# untitled.net
KiCad netlist of a schematic drawn in EAGLE
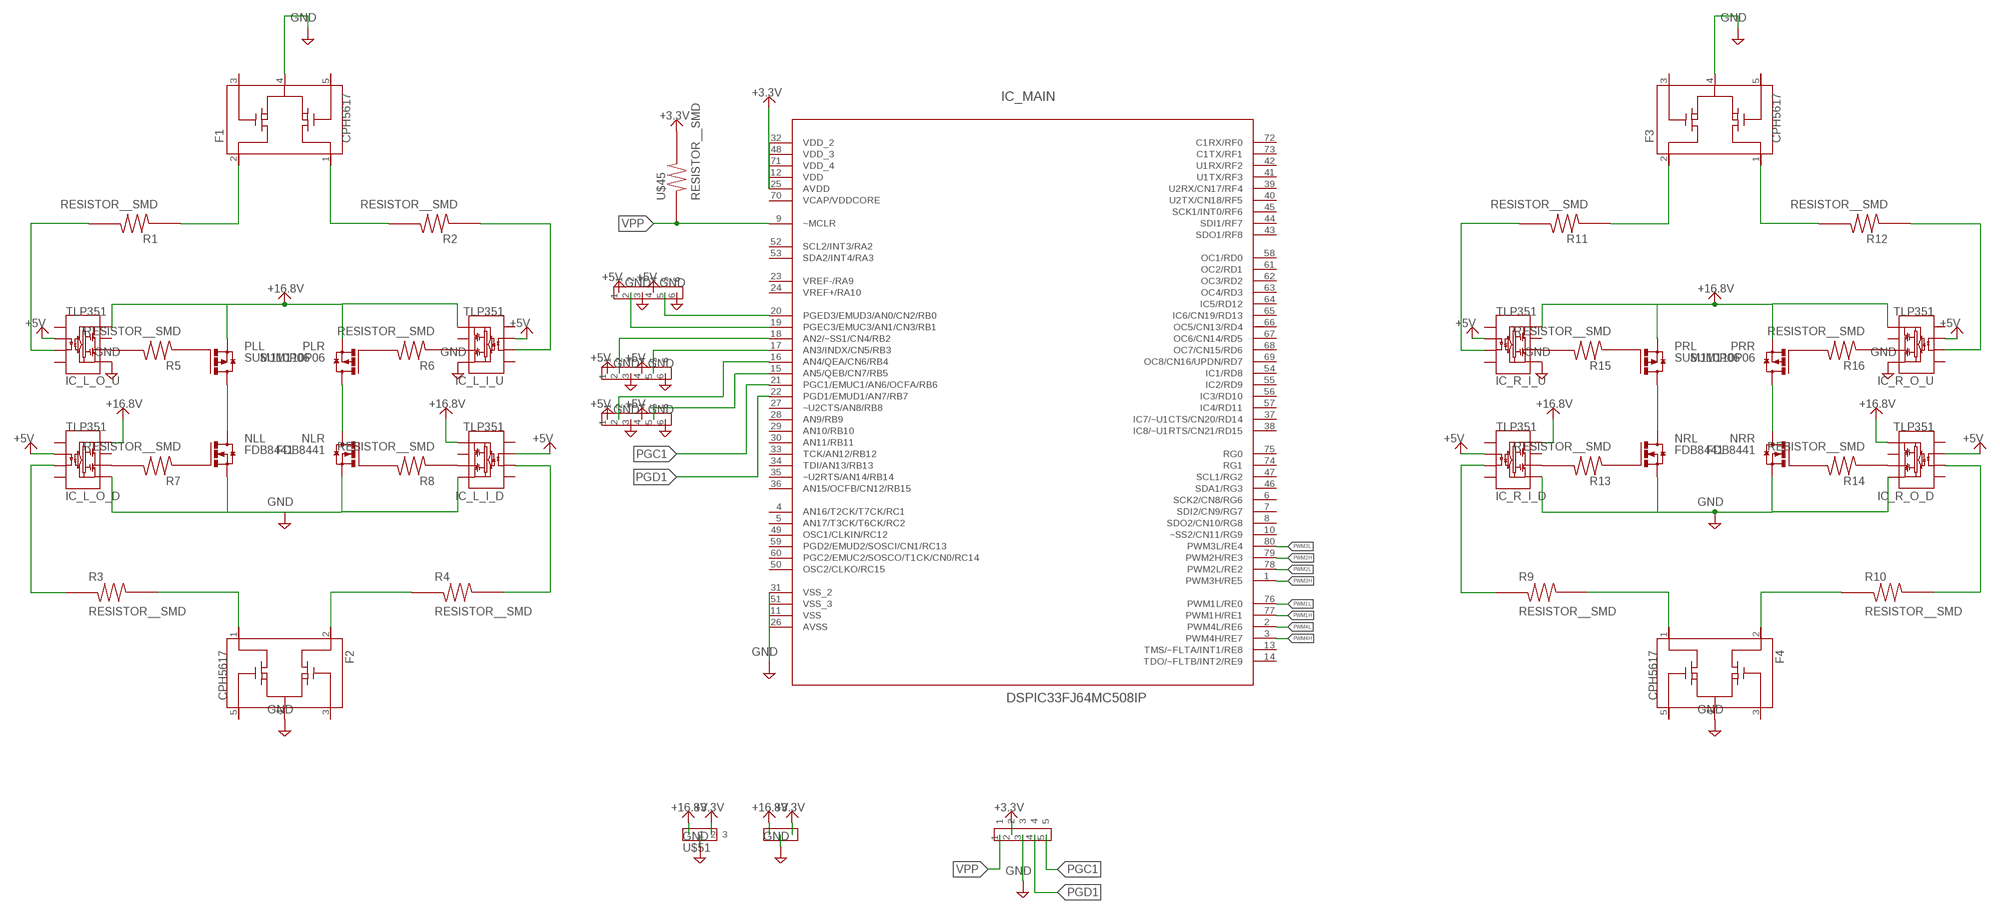
[diagram p0: schematic, sheet 1]

(export (version "E")
  (design (tool "Eeschema 10.0.6"))
  (components
    (comp (ref "F1")
      (value "CPH5617")
      (footprint "eagle-import:CHP-5")
      (libsource (lib "eagle-import") (part "CPH5617"))
    )
    (comp (ref "F2")
      (value "CPH5617")
      (footprint "eagle-import:CHP-5")
      (libsource (lib "eagle-import") (part "CPH5617"))
    )
    (comp (ref "F3")
      (value "CPH5617")
      (footprint "eagle-import:CHP-5")
      (libsource (lib "eagle-import") (part "CPH5617"))
    )
    (comp (ref "F4")
      (value "CPH5617")
      (footprint "eagle-import:CHP-5")
      (libsource (lib "eagle-import") (part "CPH5617"))
    )
    (comp (ref "IC_L_I_D")
      (value "TLP351")
      (footprint "eagle-import:DIL08")
      (libsource (lib "eagle-import") (part "TLP351"))
    )
    (comp (ref "IC_L_I_U")
      (value "TLP351")
      (footprint "eagle-import:DIL08")
      (libsource (lib "eagle-import") (part "TLP351"))
    )
    (comp (ref "IC_L_O_D")
      (value "TLP351")
      (footprint "eagle-import:DIL08")
      (libsource (lib "eagle-import") (part "TLP351"))
    )
    (comp (ref "IC_L_O_U")
      (value "TLP351")
      (footprint "eagle-import:DIL08")
      (libsource (lib "eagle-import") (part "TLP351"))
    )
    (comp (ref "IC_MAIN")
      (value "DSPIC33FJ64MC508IP")
      (footprint "eagle-import:QFP50P1400X1400X120-80N")
      (libsource (lib "eagle-import") (part "DSPIC33FJ64MC508IP"))
    )
    (comp (ref "IC_R_I_D")
      (value "TLP351")
      (footprint "eagle-import:DIL08")
      (libsource (lib "eagle-import") (part "TLP351"))
    )
    (comp (ref "IC_R_I_U")
      (value "TLP351")
      (footprint "eagle-import:DIL08")
      (libsource (lib "eagle-import") (part "TLP351"))
    )
    (comp (ref "IC_R_O_D")
      (value "TLP351")
      (footprint "eagle-import:DIL08")
      (libsource (lib "eagle-import") (part "TLP351"))
    )
    (comp (ref "IC_R_O_U")
      (value "TLP351")
      (footprint "eagle-import:DIL08")
      (libsource (lib "eagle-import") (part "TLP351"))
    )
    (comp (ref "NLL")
      (value "FDB8441")
      (footprint "eagle-import:TO-263")
      (libsource (lib "eagle-import") (part "FDB8441"))
    )
    (comp (ref "NLR")
      (value "FDB8441")
      (footprint "eagle-import:TO-263")
      (libsource (lib "eagle-import") (part "FDB8441"))
    )
    (comp (ref "NRL")
      (value "FDB8441")
      (footprint "eagle-import:TO-263")
      (libsource (lib "eagle-import") (part "FDB8441"))
    )
    (comp (ref "NRR")
      (value "FDB8441")
      (footprint "eagle-import:TO-263")
      (libsource (lib "eagle-import") (part "FDB8441"))
    )
    (comp (ref "PLL")
      (value "SUM110P06")
      (footprint "eagle-import:TO-263")
      (libsource (lib "eagle-import") (part "SUM110P06"))
    )
    (comp (ref "PLR")
      (value "SUM110P06")
      (footprint "eagle-import:TO-263")
      (libsource (lib "eagle-import") (part "SUM110P06"))
    )
    (comp (ref "PRL")
      (value "SUM110P06")
      (footprint "eagle-import:TO-263")
      (libsource (lib "eagle-import") (part "SUM110P06"))
    )
    (comp (ref "PRR")
      (value "SUM110P06")
      (footprint "eagle-import:TO-263")
      (libsource (lib "eagle-import") (part "SUM110P06"))
    )
    (comp (ref "R1")
      (value "RESISTOR__SMD")
      (footprint "eagle-import:1608")
      (libsource (lib "eagle-import") (part "RESISTOR__SMD"))
    )
    (comp (ref "R2")
      (value "RESISTOR__SMD")
      (footprint "eagle-import:1608")
      (libsource (lib "eagle-import") (part "RESISTOR__SMD"))
    )
    (comp (ref "R3")
      (value "RESISTOR__SMD")
      (footprint "eagle-import:1608")
      (libsource (lib "eagle-import") (part "RESISTOR__SMD"))
    )
    (comp (ref "R4")
      (value "RESISTOR__SMD")
      (footprint "eagle-import:1608")
      (libsource (lib "eagle-import") (part "RESISTOR__SMD"))
    )
    (comp (ref "R5")
      (value "RESISTOR__SMD")
      (footprint "eagle-import:1608")
      (libsource (lib "eagle-import") (part "RESISTOR__SMD"))
    )
    (comp (ref "R6")
      (value "RESISTOR__SMD")
      (footprint "eagle-import:1608")
      (libsource (lib "eagle-import") (part "RESISTOR__SMD"))
    )
    (comp (ref "R7")
      (value "RESISTOR__SMD")
      (footprint "eagle-import:1608")
      (libsource (lib "eagle-import") (part "RESISTOR__SMD"))
    )
    (comp (ref "R8")
      (value "RESISTOR__SMD")
      (footprint "eagle-import:1608")
      (libsource (lib "eagle-import") (part "RESISTOR__SMD"))
    )
    (comp (ref "R9")
      (value "RESISTOR__SMD")
      (footprint "eagle-import:1608")
      (libsource (lib "eagle-import") (part "RESISTOR__SMD"))
    )
    (comp (ref "R10")
      (value "RESISTOR__SMD")
      (footprint "eagle-import:1608")
      (libsource (lib "eagle-import") (part "RESISTOR__SMD"))
    )
    (comp (ref "R11")
      (value "RESISTOR__SMD")
      (footprint "eagle-import:1608")
      (libsource (lib "eagle-import") (part "RESISTOR__SMD"))
    )
    (comp (ref "R12")
      (value "RESISTOR__SMD")
      (footprint "eagle-import:1608")
      (libsource (lib "eagle-import") (part "RESISTOR__SMD"))
    )
    (comp (ref "R13")
      (value "RESISTOR__SMD")
      (footprint "eagle-import:1608")
      (libsource (lib "eagle-import") (part "RESISTOR__SMD"))
    )
    (comp (ref "R14")
      (value "RESISTOR__SMD")
      (footprint "eagle-import:1608")
      (libsource (lib "eagle-import") (part "RESISTOR__SMD"))
    )
    (comp (ref "R15")
      (value "RESISTOR__SMD")
      (footprint "eagle-import:1608")
      (libsource (lib "eagle-import") (part "RESISTOR__SMD"))
    )
    (comp (ref "R16")
      (value "RESISTOR__SMD")
      (footprint "eagle-import:1608")
      (libsource (lib "eagle-import") (part "RESISTOR__SMD"))
    )
    (comp (ref "U$1")
      (value "PIN_HEADER_5")
      (footprint "eagle-import:PIN_HEADER_5")
      (libsource (lib "eagle-import") (part "PIN_HEADER_5"))
    )
    (comp (ref "U$4")
      (value "PIN_HEADER_6")
      (footprint "eagle-import:PIN_HEADER_6")
      (libsource (lib "eagle-import") (part "PIN_HEADER_6"))
    )
    (comp (ref "U$5")
      (value "PIN_HEADER_6")
      (footprint "eagle-import:PIN_HEADER_6")
      (libsource (lib "eagle-import") (part "PIN_HEADER_6"))
    )
    (comp (ref "U$20")
      (value "PIN_HEADER_6")
      (footprint "eagle-import:PIN_HEADER_6")
      (libsource (lib "eagle-import") (part "PIN_HEADER_6"))
    )
    (comp (ref "U$45")
      (value "RESISTOR__SMD")
      (footprint "eagle-import:1608")
      (libsource (lib "eagle-import") (part "RESISTOR__SMD"))
    )
    (comp (ref "U$47")
      (value "TA48M05")
      (footprint "eagle-import:ＨＳＩＰ３")
      (libsource (lib "eagle-import") (part "TA48M05"))
    )
    (comp (ref "U$51")
      (value "TA48M033")
      (footprint "eagle-import:ＨＳＩＰ３")
      (libsource (lib "eagle-import") (part "TA48M033"))
    )
  )
  (nets
    (net (code "1") (name "+3.3V") (class "Default")
      (node (ref "IC_MAIN") (pin "12") (pinfunction "VDD_12") (pintype "power_in"))
      (node (ref "IC_MAIN") (pin "25") (pinfunction "AVDD_25") (pintype "power_in"))
      (node (ref "IC_MAIN") (pin "32") (pinfunction "VDD_2_32") (pintype "power_in"))
      (node (ref "IC_MAIN") (pin "48") (pinfunction "VDD_3_48") (pintype "power_in"))
      (node (ref "IC_MAIN") (pin "71") (pinfunction "VDD_4_71") (pintype "power_in"))
      (node (ref "U$1") (pin "2") (pinfunction "2_2") (pintype "bidirectional"))
      (node (ref "U$45") (pin "2") (pinfunction "P$2_2") (pintype "passive"))
      (node (ref "U$47") (pin "3") (pinfunction "OUT_3") (pintype "bidirectional"))
      (node (ref "U$51") (pin "3") (pinfunction "3_3") (pintype "bidirectional"))
    )
    (net (code "2") (name "+5V") (class "Default")
      (node (ref "IC_L_I_D") (pin "2") (pinfunction "LED+_2") (pintype "bidirectional"))
      (node (ref "IC_L_I_U") (pin "2") (pinfunction "LED+_2") (pintype "bidirectional"))
      (node (ref "IC_L_O_D") (pin "2") (pinfunction "LED+_2") (pintype "bidirectional"))
      (node (ref "IC_L_O_U") (pin "2") (pinfunction "LED+_2") (pintype "bidirectional"))
      (node (ref "IC_R_I_D") (pin "2") (pinfunction "LED+_2") (pintype "bidirectional"))
      (node (ref "IC_R_I_U") (pin "2") (pinfunction "LED+_2") (pintype "bidirectional"))
      (node (ref "IC_R_O_D") (pin "2") (pinfunction "LED+_2") (pintype "bidirectional"))
      (node (ref "IC_R_O_U") (pin "2") (pinfunction "LED+_2") (pintype "bidirectional"))
      (node (ref "U$20") (pin "1") (pinfunction "1_1") (pintype "bidirectional"))
      (node (ref "U$20") (pin "4") (pinfunction "4_4") (pintype "bidirectional"))
      (node (ref "U$4") (pin "1") (pinfunction "1_1") (pintype "bidirectional"))
      (node (ref "U$4") (pin "4") (pinfunction "4_4") (pintype "bidirectional"))
      (node (ref "U$5") (pin "1") (pinfunction "1_1") (pintype "bidirectional"))
      (node (ref "U$5") (pin "4") (pinfunction "4_4") (pintype "bidirectional"))
    )
    (net (code "3") (name "+16.8V") (class "Default")
      (node (ref "IC_L_I_D") (pin "8") (pinfunction "VDD_8") (pintype "bidirectional"))
      (node (ref "IC_L_I_U") (pin "8") (pinfunction "VDD_8") (pintype "bidirectional"))
      (node (ref "IC_L_O_D") (pin "8") (pinfunction "VDD_8") (pintype "bidirectional"))
      (node (ref "IC_L_O_U") (pin "8") (pinfunction "VDD_8") (pintype "bidirectional"))
      (node (ref "IC_R_I_D") (pin "8") (pinfunction "VDD_8") (pintype "bidirectional"))
      (node (ref "IC_R_I_U") (pin "8") (pinfunction "VDD_8") (pintype "bidirectional"))
      (node (ref "IC_R_O_D") (pin "8") (pinfunction "VDD_8") (pintype "bidirectional"))
      (node (ref "IC_R_O_U") (pin "8") (pinfunction "VDD_8") (pintype "bidirectional"))
      (node (ref "PLL") (pin "2") (pinfunction "S_2") (pintype "passive"))
      (node (ref "PLR") (pin "2") (pinfunction "S_2") (pintype "passive"))
      (node (ref "PRL") (pin "2") (pinfunction "S_2") (pintype "passive"))
      (node (ref "PRR") (pin "2") (pinfunction "S_2") (pintype "passive"))
      (node (ref "U$47") (pin "1") (pinfunction "IN_1") (pintype "bidirectional"))
      (node (ref "U$51") (pin "1") (pinfunction "1_1") (pintype "bidirectional"))
    )
    (net (code "4") (name "/VCAP{slash}VDDCORE") (class "Default")
      (node (ref "IC_MAIN") (pin "70") (pinfunction "VCAP/VDDCORE_70") (pintype "power_in"))
    )
    (net (code "5") (name "GND") (class "Default")
      (node (ref "F1") (pin "4") (pinfunction "S_4") (pintype "bidirectional"))
      (node (ref "F2") (pin "4") (pinfunction "S_4") (pintype "bidirectional"))
      (node (ref "F3") (pin "4") (pinfunction "S_4") (pintype "bidirectional"))
      (node (ref "F4") (pin "4") (pinfunction "S_4") (pintype "bidirectional"))
      (node (ref "IC_L_I_D") (pin "5") (pinfunction "GND_5") (pintype "bidirectional"))
      (node (ref "IC_L_I_U") (pin "5") (pinfunction "GND_5") (pintype "bidirectional"))
      (node (ref "IC_L_O_D") (pin "5") (pinfunction "GND_5") (pintype "bidirectional"))
      (node (ref "IC_L_O_U") (pin "5") (pinfunction "GND_5") (pintype "bidirectional"))
      (node (ref "IC_MAIN") (pin "11") (pinfunction "VSS_11") (pintype "power_in"))
      (node (ref "IC_MAIN") (pin "26") (pinfunction "AVSS_26") (pintype "power_in"))
      (node (ref "IC_MAIN") (pin "31") (pinfunction "VSS_2_31") (pintype "power_in"))
      (node (ref "IC_MAIN") (pin "51") (pinfunction "VSS_3_51") (pintype "power_in"))
      (node (ref "IC_R_I_D") (pin "5") (pinfunction "GND_5") (pintype "bidirectional"))
      (node (ref "IC_R_I_U") (pin "5") (pinfunction "GND_5") (pintype "bidirectional"))
      (node (ref "IC_R_O_D") (pin "5") (pinfunction "GND_5") (pintype "bidirectional"))
      (node (ref "IC_R_O_U") (pin "5") (pinfunction "GND_5") (pintype "bidirectional"))
      (node (ref "NLL") (pin "2") (pinfunction "S_2") (pintype "passive"))
      (node (ref "NLR") (pin "2") (pinfunction "S_2") (pintype "passive"))
      (node (ref "NRL") (pin "2") (pinfunction "S_2") (pintype "passive"))
      (node (ref "NRR") (pin "2") (pinfunction "S_2") (pintype "passive"))
      (node (ref "U$1") (pin "3") (pinfunction "3_3") (pintype "bidirectional"))
      (node (ref "U$20") (pin "3") (pinfunction "3_3") (pintype "bidirectional"))
      (node (ref "U$20") (pin "6") (pinfunction "6_6") (pintype "bidirectional"))
      (node (ref "U$4") (pin "3") (pinfunction "3_3") (pintype "bidirectional"))
      (node (ref "U$4") (pin "6") (pinfunction "6_6") (pintype "bidirectional"))
      (node (ref "U$47") (pin "2") (pinfunction "GND_2") (pintype "bidirectional"))
      (node (ref "U$5") (pin "3") (pinfunction "3_3") (pintype "bidirectional"))
      (node (ref "U$5") (pin "6") (pinfunction "6_6") (pintype "bidirectional"))
      (node (ref "U$51") (pin "2") (pinfunction "2_2") (pintype "bidirectional"))
    )
    (net (code "6") (name "Net-(F1-D1)") (class "Default")
      (node (ref "F1") (pin "1") (pinfunction "D1_1") (pintype "bidirectional"))
      (node (ref "R2") (pin "2") (pinfunction "P$2_2") (pintype "passive"))
    )
    (net (code "7") (name "Net-(F1-D2)") (class "Default")
      (node (ref "F1") (pin "2") (pinfunction "D2_2") (pintype "bidirectional"))
      (node (ref "R1") (pin "1") (pinfunction "P$1_1") (pintype "passive"))
    )
    (net (code "8") (name "Net-(F2-D1)") (class "Default")
      (node (ref "F2") (pin "1") (pinfunction "D1_1") (pintype "bidirectional"))
      (node (ref "R3") (pin "2") (pinfunction "P$2_2") (pintype "passive"))
    )
    (net (code "9") (name "Net-(F2-D2)") (class "Default")
      (node (ref "F2") (pin "2") (pinfunction "D2_2") (pintype "bidirectional"))
      (node (ref "R4") (pin "1") (pinfunction "P$1_1") (pintype "passive"))
    )
    (net (code "10") (name "Net-(F3-D1)") (class "Default")
      (node (ref "F3") (pin "1") (pinfunction "D1_1") (pintype "bidirectional"))
      (node (ref "R12") (pin "2") (pinfunction "P$2_2") (pintype "passive"))
    )
    (net (code "11") (name "Net-(F3-D2)") (class "Default")
      (node (ref "F3") (pin "2") (pinfunction "D2_2") (pintype "bidirectional"))
      (node (ref "R11") (pin "1") (pinfunction "P$1_1") (pintype "passive"))
    )
    (net (code "12") (name "Net-(F4-D1)") (class "Default")
      (node (ref "F4") (pin "1") (pinfunction "D1_1") (pintype "bidirectional"))
      (node (ref "R9") (pin "2") (pinfunction "P$2_2") (pintype "passive"))
    )
    (net (code "13") (name "Net-(F4-D2)") (class "Default")
      (node (ref "F4") (pin "2") (pinfunction "D2_2") (pintype "bidirectional"))
      (node (ref "R10") (pin "1") (pinfunction "P$1_1") (pintype "passive"))
    )
    (net (code "14") (name "Net-(IC_L_I_D-LED-)") (class "Default")
      (node (ref "IC_L_I_D") (pin "3") (pinfunction "LED-_3") (pintype "bidirectional"))
      (node (ref "R4") (pin "2") (pinfunction "P$2_2") (pintype "passive"))
    )
    (net (code "15") (name "Net-(IC_L_I_D-OUT)") (class "Default")
      (node (ref "IC_L_I_D") (pin "6") (pinfunction "OUT_6") (pintype "output"))
      (node (ref "R8") (pin "1") (pinfunction "P$1_1") (pintype "passive"))
    )
    (net (code "16") (name "Net-(IC_L_I_U-LED-)") (class "Default")
      (node (ref "IC_L_I_U") (pin "3") (pinfunction "LED-_3") (pintype "bidirectional"))
      (node (ref "R2") (pin "1") (pinfunction "P$1_1") (pintype "passive"))
    )
    (net (code "17") (name "Net-(IC_L_I_U-OUT)") (class "Default")
      (node (ref "IC_L_I_U") (pin "6") (pinfunction "OUT_6") (pintype "output"))
      (node (ref "R6") (pin "1") (pinfunction "P$1_1") (pintype "passive"))
    )
    (net (code "18") (name "Net-(IC_L_O_D-LED-)") (class "Default")
      (node (ref "IC_L_O_D") (pin "3") (pinfunction "LED-_3") (pintype "bidirectional"))
      (node (ref "R3") (pin "1") (pinfunction "P$1_1") (pintype "passive"))
    )
    (net (code "19") (name "Net-(IC_L_O_D-OUT)") (class "Default")
      (node (ref "IC_L_O_D") (pin "6") (pinfunction "OUT_6") (pintype "output"))
      (node (ref "R7") (pin "2") (pinfunction "P$2_2") (pintype "passive"))
    )
    (net (code "20") (name "Net-(IC_L_O_U-LED-)") (class "Default")
      (node (ref "IC_L_O_U") (pin "3") (pinfunction "LED-_3") (pintype "bidirectional"))
      (node (ref "R1") (pin "2") (pinfunction "P$2_2") (pintype "passive"))
    )
    (net (code "21") (name "Net-(IC_L_O_U-OUT)") (class "Default")
      (node (ref "IC_L_O_U") (pin "6") (pinfunction "OUT_6") (pintype "output"))
      (node (ref "R5") (pin "2") (pinfunction "P$2_2") (pintype "passive"))
    )
    (net (code "22") (name "Net-(IC_MAIN-AN2{slash}~{SS1{slash}CN4{slash}RB2})") (class "Default")
      (node (ref "IC_MAIN") (pin "18") (pinfunction "AN2/~{SS1/CN4/RB2}_18") (pintype "bidirectional"))
      (node (ref "U$5") (pin "2") (pinfunction "2_2") (pintype "bidirectional"))
    )
    (net (code "23") (name "Net-(IC_MAIN-AN3{slash}INDX{slash}CN5{slash}RB3)") (class "Default")
      (node (ref "IC_MAIN") (pin "17") (pinfunction "AN3/INDX/CN5/RB3_17") (pintype "bidirectional"))
      (node (ref "U$5") (pin "5") (pinfunction "5_5") (pintype "bidirectional"))
    )
    (net (code "24") (name "Net-(IC_MAIN-AN4{slash}QEA{slash}CN6{slash}RB4)") (class "Default")
      (node (ref "IC_MAIN") (pin "16") (pinfunction "AN4/QEA/CN6/RB4_16") (pintype "bidirectional"))
      (node (ref "U$20") (pin "2") (pinfunction "2_2") (pintype "bidirectional"))
    )
    (net (code "25") (name "Net-(IC_MAIN-AN5{slash}QEB{slash}CN7{slash}RB5)") (class "Default")
      (node (ref "IC_MAIN") (pin "15") (pinfunction "AN5/QEB/CN7/RB5_15") (pintype "bidirectional"))
      (node (ref "U$20") (pin "5") (pinfunction "5_5") (pintype "bidirectional"))
    )
    (net (code "26") (name "Net-(IC_MAIN-PGEC3{slash}EMUC3{slash}AN1{slash}CN3{slash}RB1)") (class "Default")
      (node (ref "IC_MAIN") (pin "19") (pinfunction "PGEC3/EMUC3/AN1/CN3/RB1_19") (pintype "bidirectional"))
      (node (ref "U$4") (pin "2") (pinfunction "2_2") (pintype "bidirectional"))
    )
    (net (code "27") (name "Net-(IC_MAIN-PGED3{slash}EMUD3{slash}AN0{slash}CN2{slash}RB0)") (class "Default")
      (node (ref "IC_MAIN") (pin "20") (pinfunction "PGED3/EMUD3/AN0/CN2/RB0_20") (pintype "bidirectional"))
      (node (ref "U$4") (pin "5") (pinfunction "5_5") (pintype "bidirectional"))
    )
    (net (code "28") (name "Net-(IC_R_I_D-LED-)") (class "Default")
      (node (ref "IC_R_I_D") (pin "3") (pinfunction "LED-_3") (pintype "bidirectional"))
      (node (ref "R9") (pin "1") (pinfunction "P$1_1") (pintype "passive"))
    )
    (net (code "29") (name "Net-(IC_R_I_D-OUT)") (class "Default")
      (node (ref "IC_R_I_D") (pin "6") (pinfunction "OUT_6") (pintype "output"))
      (node (ref "R13") (pin "2") (pinfunction "P$2_2") (pintype "passive"))
    )
    (net (code "30") (name "Net-(IC_R_I_U-LED-)") (class "Default")
      (node (ref "IC_R_I_U") (pin "3") (pinfunction "LED-_3") (pintype "bidirectional"))
      (node (ref "R11") (pin "2") (pinfunction "P$2_2") (pintype "passive"))
    )
    (net (code "31") (name "Net-(IC_R_I_U-OUT)") (class "Default")
      (node (ref "IC_R_I_U") (pin "6") (pinfunction "OUT_6") (pintype "output"))
      (node (ref "R15") (pin "2") (pinfunction "P$2_2") (pintype "passive"))
    )
    (net (code "32") (name "Net-(IC_R_O_D-LED-)") (class "Default")
      (node (ref "IC_R_O_D") (pin "3") (pinfunction "LED-_3") (pintype "bidirectional"))
      (node (ref "R10") (pin "2") (pinfunction "P$2_2") (pintype "passive"))
    )
    (net (code "33") (name "Net-(IC_R_O_D-OUT)") (class "Default")
      (node (ref "IC_R_O_D") (pin "6") (pinfunction "OUT_6") (pintype "output"))
      (node (ref "R14") (pin "1") (pinfunction "P$1_1") (pintype "passive"))
    )
    (net (code "34") (name "Net-(IC_R_O_U-LED-)") (class "Default")
      (node (ref "IC_R_O_U") (pin "3") (pinfunction "LED-_3") (pintype "bidirectional"))
      (node (ref "R12") (pin "1") (pinfunction "P$1_1") (pintype "passive"))
    )
    (net (code "35") (name "Net-(IC_R_O_U-OUT)") (class "Default")
      (node (ref "IC_R_O_U") (pin "6") (pinfunction "OUT_6") (pintype "output"))
      (node (ref "R16") (pin "1") (pinfunction "P$1_1") (pintype "passive"))
    )
    (net (code "36") (name "Net-(NLL-D)") (class "Default")
      (node (ref "NLL") (pin "3") (pinfunction "D_3") (pintype "passive"))
      (node (ref "PLL") (pin "3") (pinfunction "D_3") (pintype "passive"))
    )
    (net (code "37") (name "Net-(NLL-G)") (class "Default")
      (node (ref "NLL") (pin "1") (pinfunction "G_1") (pintype "passive"))
      (node (ref "R7") (pin "1") (pinfunction "P$1_1") (pintype "passive"))
    )
    (net (code "38") (name "Net-(NLR-D)") (class "Default")
      (node (ref "NLR") (pin "3") (pinfunction "D_3") (pintype "passive"))
      (node (ref "PLR") (pin "3") (pinfunction "D_3") (pintype "passive"))
    )
    (net (code "39") (name "Net-(NLR-G)") (class "Default")
      (node (ref "NLR") (pin "1") (pinfunction "G_1") (pintype "passive"))
      (node (ref "R8") (pin "2") (pinfunction "P$2_2") (pintype "passive"))
    )
    (net (code "40") (name "Net-(NRL-D)") (class "Default")
      (node (ref "NRL") (pin "3") (pinfunction "D_3") (pintype "passive"))
      (node (ref "PRL") (pin "3") (pinfunction "D_3") (pintype "passive"))
    )
    (net (code "41") (name "Net-(NRL-G)") (class "Default")
      (node (ref "NRL") (pin "1") (pinfunction "G_1") (pintype "passive"))
      (node (ref "R13") (pin "1") (pinfunction "P$1_1") (pintype "passive"))
    )
    (net (code "42") (name "Net-(NRR-D)") (class "Default")
      (node (ref "NRR") (pin "3") (pinfunction "D_3") (pintype "passive"))
      (node (ref "PRR") (pin "3") (pinfunction "D_3") (pintype "passive"))
    )
    (net (code "43") (name "Net-(NRR-G)") (class "Default")
      (node (ref "NRR") (pin "1") (pinfunction "G_1") (pintype "passive"))
      (node (ref "R14") (pin "2") (pinfunction "P$2_2") (pintype "passive"))
    )
    (net (code "44") (name "Net-(PLL-G)") (class "Default")
      (node (ref "PLL") (pin "1") (pinfunction "G_1") (pintype "passive"))
      (node (ref "R5") (pin "1") (pinfunction "P$1_1") (pintype "passive"))
    )
    (net (code "45") (name "Net-(PLR-G)") (class "Default")
      (node (ref "PLR") (pin "1") (pinfunction "G_1") (pintype "passive"))
      (node (ref "R6") (pin "2") (pinfunction "P$2_2") (pintype "passive"))
    )
    (net (code "46") (name "Net-(PRL-G)") (class "Default")
      (node (ref "PRL") (pin "1") (pinfunction "G_1") (pintype "passive"))
      (node (ref "R15") (pin "1") (pinfunction "P$1_1") (pintype "passive"))
    )
    (net (code "47") (name "Net-(PRR-G)") (class "Default")
      (node (ref "PRR") (pin "1") (pinfunction "G_1") (pintype "passive"))
      (node (ref "R16") (pin "2") (pinfunction "P$2_2") (pintype "passive"))
    )
    (net (code "48") (name "PGC1") (class "Default")
      (node (ref "IC_MAIN") (pin "21") (pinfunction "PGC1/EMUC1/AN6/OCFA/RB6_21") (pintype "bidirectional"))
      (node (ref "U$1") (pin "5") (pinfunction "5_5") (pintype "bidirectional"))
    )
    (net (code "49") (name "PGD1") (class "Default")
      (node (ref "IC_MAIN") (pin "22") (pinfunction "PGD1/EMUD1/AN7/RB7_22") (pintype "bidirectional"))
      (node (ref "U$1") (pin "4") (pinfunction "4_4") (pintype "bidirectional"))
    )
    (net (code "50") (name "PWM1H") (class "Default")
      (node (ref "IC_MAIN") (pin "77") (pinfunction "PWM1H/RE1_77") (pintype "bidirectional"))
    )
    (net (code "51") (name "PWM1L") (class "Default")
      (node (ref "IC_MAIN") (pin "76") (pinfunction "PWM1L/RE0_76") (pintype "bidirectional"))
    )
    (net (code "52") (name "PWM2H") (class "Default")
      (node (ref "IC_MAIN") (pin "79") (pinfunction "PWM2H/RE3_79") (pintype "bidirectional"))
    )
    (net (code "53") (name "PWM2L") (class "Default")
      (node (ref "IC_MAIN") (pin "78") (pinfunction "PWM2L/RE2_78") (pintype "bidirectional"))
    )
    (net (code "54") (name "PWM3H") (class "Default")
      (node (ref "IC_MAIN") (pin "1") (pinfunction "PWM3H/RE5_1") (pintype "bidirectional"))
    )
    (net (code "55") (name "PWM3L") (class "Default")
      (node (ref "IC_MAIN") (pin "80") (pinfunction "PWM3L/RE4_80") (pintype "bidirectional"))
    )
    (net (code "56") (name "PWM4H") (class "Default")
      (node (ref "IC_MAIN") (pin "3") (pinfunction "PWM4H/RE7_3") (pintype "bidirectional"))
    )
    (net (code "57") (name "PWM4L") (class "Default")
      (node (ref "IC_MAIN") (pin "2") (pinfunction "PWM4L/RE6_2") (pintype "bidirectional"))
    )
    (net (code "58") (name "VPP") (class "Default")
      (node (ref "IC_MAIN") (pin "9") (pinfunction "~{MCLR}_9") (pintype "input"))
      (node (ref "U$1") (pin "1") (pinfunction "1_1") (pintype "bidirectional"))
      (node (ref "U$45") (pin "1") (pinfunction "P$1_1") (pintype "passive"))
    )
    (net (code "59") (name "unconnected-(F1-G1-Pad5)") (class "Default")
      (node (ref "F1") (pin "5") (pinfunction "G1_5") (pintype "bidirectional"))
    )
    (net (code "60") (name "unconnected-(F1-G2-Pad3)") (class "Default")
      (node (ref "F1") (pin "3") (pinfunction "G2_3") (pintype "bidirectional"))
    )
    (net (code "61") (name "unconnected-(F2-G1-Pad5)") (class "Default")
      (node (ref "F2") (pin "5") (pinfunction "G1_5") (pintype "bidirectional"))
    )
    (net (code "62") (name "unconnected-(F2-G2-Pad3)") (class "Default")
      (node (ref "F2") (pin "3") (pinfunction "G2_3") (pintype "bidirectional"))
    )
    (net (code "63") (name "unconnected-(F3-G1-Pad5)") (class "Default")
      (node (ref "F3") (pin "5") (pinfunction "G1_5") (pintype "bidirectional"))
    )
    (net (code "64") (name "unconnected-(F3-G2-Pad3)") (class "Default")
      (node (ref "F3") (pin "3") (pinfunction "G2_3") (pintype "bidirectional"))
    )
    (net (code "65") (name "unconnected-(F4-G1-Pad5)") (class "Default")
      (node (ref "F4") (pin "5") (pinfunction "G1_5") (pintype "bidirectional"))
    )
    (net (code "66") (name "unconnected-(F4-G2-Pad3)") (class "Default")
      (node (ref "F4") (pin "3") (pinfunction "G2_3") (pintype "bidirectional"))
    )
    (net (code "67") (name "unconnected-(IC_L_I_D-NC1-Pad1)") (class "Default")
      (node (ref "IC_L_I_D") (pin "1") (pinfunction "NC1_1") (pintype "no_connect"))
    )
    (net (code "68") (name "unconnected-(IC_L_I_D-NC4-Pad4)") (class "Default")
      (node (ref "IC_L_I_D") (pin "4") (pinfunction "NC4_4") (pintype "no_connect"))
    )
    (net (code "69") (name "unconnected-(IC_L_I_D-NC7-Pad7)") (class "Default")
      (node (ref "IC_L_I_D") (pin "7") (pinfunction "NC7_7") (pintype "no_connect"))
    )
    (net (code "70") (name "unconnected-(IC_L_I_U-NC1-Pad1)") (class "Default")
      (node (ref "IC_L_I_U") (pin "1") (pinfunction "NC1_1") (pintype "no_connect"))
    )
    (net (code "71") (name "unconnected-(IC_L_I_U-NC4-Pad4)") (class "Default")
      (node (ref "IC_L_I_U") (pin "4") (pinfunction "NC4_4") (pintype "no_connect"))
    )
    (net (code "72") (name "unconnected-(IC_L_I_U-NC7-Pad7)") (class "Default")
      (node (ref "IC_L_I_U") (pin "7") (pinfunction "NC7_7") (pintype "no_connect"))
    )
    (net (code "73") (name "unconnected-(IC_L_O_D-NC1-Pad1)") (class "Default")
      (node (ref "IC_L_O_D") (pin "1") (pinfunction "NC1_1") (pintype "no_connect"))
    )
    (net (code "74") (name "unconnected-(IC_L_O_D-NC4-Pad4)") (class "Default")
      (node (ref "IC_L_O_D") (pin "4") (pinfunction "NC4_4") (pintype "no_connect"))
    )
    (net (code "75") (name "unconnected-(IC_L_O_D-NC7-Pad7)") (class "Default")
      (node (ref "IC_L_O_D") (pin "7") (pinfunction "NC7_7") (pintype "no_connect"))
    )
    (net (code "76") (name "unconnected-(IC_L_O_U-NC1-Pad1)") (class "Default")
      (node (ref "IC_L_O_U") (pin "1") (pinfunction "NC1_1") (pintype "no_connect"))
    )
    (net (code "77") (name "unconnected-(IC_L_O_U-NC4-Pad4)") (class "Default")
      (node (ref "IC_L_O_U") (pin "4") (pinfunction "NC4_4") (pintype "no_connect"))
    )
    (net (code "78") (name "unconnected-(IC_L_O_U-NC7-Pad7)") (class "Default")
      (node (ref "IC_L_O_U") (pin "7") (pinfunction "NC7_7") (pintype "no_connect"))
    )
    (net (code "79") (name "unconnected-(IC_MAIN-AN9{slash}RB9-Pad28)") (class "Default")
      (node (ref "IC_MAIN") (pin "28") (pinfunction "AN9/RB9_28") (pintype "bidirectional"))
    )
    (net (code "80") (name "unconnected-(IC_MAIN-AN10{slash}RB10-Pad29)") (class "Default")
      (node (ref "IC_MAIN") (pin "29") (pinfunction "AN10/RB10_29") (pintype "bidirectional"))
    )
    (net (code "81") (name "unconnected-(IC_MAIN-AN11{slash}RB11-Pad30)") (class "Default")
      (node (ref "IC_MAIN") (pin "30") (pinfunction "AN11/RB11_30") (pintype "bidirectional"))
    )
    (net (code "82") (name "unconnected-(IC_MAIN-AN15{slash}OCFB{slash}CN12{slash}RB15-Pad36)") (class "Default")
      (node (ref "IC_MAIN") (pin "36") (pinfunction "AN15/OCFB/CN12/RB15_36") (pintype "bidirectional"))
    )
    (net (code "83") (name "unconnected-(IC_MAIN-AN16{slash}T2CK{slash}T7CK{slash}RC1-Pad4)") (class "Default")
      (node (ref "IC_MAIN") (pin "4") (pinfunction "AN16/T2CK/T7CK/RC1_4") (pintype "bidirectional"))
    )
    (net (code "84") (name "unconnected-(IC_MAIN-AN17{slash}T3CK{slash}T6CK{slash}RC2-Pad5)") (class "Default")
      (node (ref "IC_MAIN") (pin "5") (pinfunction "AN17/T3CK/T6CK/RC2_5") (pintype "bidirectional"))
    )
    (net (code "85") (name "unconnected-(IC_MAIN-C1RX{slash}RF0-Pad72)") (class "Default")
      (node (ref "IC_MAIN") (pin "72") (pinfunction "C1RX/RF0_72") (pintype "bidirectional"))
    )
    (net (code "86") (name "unconnected-(IC_MAIN-C1TX{slash}RF1-Pad73)") (class "Default")
      (node (ref "IC_MAIN") (pin "73") (pinfunction "C1TX/RF1_73") (pintype "bidirectional"))
    )
    (net (code "87") (name "unconnected-(IC_MAIN-IC1{slash}RD8-Pad54)") (class "Default")
      (node (ref "IC_MAIN") (pin "54") (pinfunction "IC1/RD8_54") (pintype "bidirectional"))
    )
    (net (code "88") (name "unconnected-(IC_MAIN-IC2{slash}RD9-Pad55)") (class "Default")
      (node (ref "IC_MAIN") (pin "55") (pinfunction "IC2/RD9_55") (pintype "bidirectional"))
    )
    (net (code "89") (name "unconnected-(IC_MAIN-IC3{slash}RD10-Pad56)") (class "Default")
      (node (ref "IC_MAIN") (pin "56") (pinfunction "IC3/RD10_56") (pintype "bidirectional"))
    )
    (net (code "90") (name "unconnected-(IC_MAIN-IC4{slash}RD11-Pad57)") (class "Default")
      (node (ref "IC_MAIN") (pin "57") (pinfunction "IC4/RD11_57") (pintype "bidirectional"))
    )
    (net (code "91") (name "unconnected-(IC_MAIN-IC5{slash}RD12-Pad64)") (class "Default")
      (node (ref "IC_MAIN") (pin "64") (pinfunction "IC5/RD12_64") (pintype "bidirectional"))
    )
    (net (code "92") (name "unconnected-(IC_MAIN-IC6{slash}CN19{slash}RD13-Pad65)") (class "Default")
      (node (ref "IC_MAIN") (pin "65") (pinfunction "IC6/CN19/RD13_65") (pintype "bidirectional"))
    )
    (net (code "93") (name "unconnected-(IC_MAIN-IC7{slash}~{U1CTS{slash}CN20{slash}RD14}-Pad37)") (class "Default")
      (node (ref "IC_MAIN") (pin "37") (pinfunction "IC7/~{U1CTS/CN20/RD14}_37") (pintype "bidirectional"))
    )
    (net (code "94") (name "unconnected-(IC_MAIN-IC8{slash}~{U1RTS{slash}CN21{slash}RD15}-Pad38)") (class "Default")
      (node (ref "IC_MAIN") (pin "38") (pinfunction "IC8/~{U1RTS/CN21/RD15}_38") (pintype "bidirectional"))
    )
    (net (code "95") (name "unconnected-(IC_MAIN-OC1{slash}RD0-Pad58)") (class "Default")
      (node (ref "IC_MAIN") (pin "58") (pinfunction "OC1/RD0_58") (pintype "bidirectional"))
    )
    (net (code "96") (name "unconnected-(IC_MAIN-OC2{slash}RD1-Pad61)") (class "Default")
      (node (ref "IC_MAIN") (pin "61") (pinfunction "OC2/RD1_61") (pintype "bidirectional"))
    )
    (net (code "97") (name "unconnected-(IC_MAIN-OC3{slash}RD2-Pad62)") (class "Default")
      (node (ref "IC_MAIN") (pin "62") (pinfunction "OC3/RD2_62") (pintype "bidirectional"))
    )
    (net (code "98") (name "unconnected-(IC_MAIN-OC4{slash}RD3-Pad63)") (class "Default")
      (node (ref "IC_MAIN") (pin "63") (pinfunction "OC4/RD3_63") (pintype "bidirectional"))
    )
    (net (code "99") (name "unconnected-(IC_MAIN-OC5{slash}CN13{slash}RD4-Pad66)") (class "Default")
      (node (ref "IC_MAIN") (pin "66") (pinfunction "OC5/CN13/RD4_66") (pintype "bidirectional"))
    )
    (net (code "100") (name "unconnected-(IC_MAIN-OC6{slash}CN14{slash}RD5-Pad67)") (class "Default")
      (node (ref "IC_MAIN") (pin "67") (pinfunction "OC6/CN14/RD5_67") (pintype "bidirectional"))
    )
    (net (code "101") (name "unconnected-(IC_MAIN-OC7{slash}CN15{slash}RD6-Pad68)") (class "Default")
      (node (ref "IC_MAIN") (pin "68") (pinfunction "OC7/CN15/RD6_68") (pintype "bidirectional"))
    )
    (net (code "102") (name "unconnected-(IC_MAIN-OC8{slash}CN16{slash}UPDN{slash}RD7-Pad69)") (class "Default")
      (node (ref "IC_MAIN") (pin "69") (pinfunction "OC8/CN16/UPDN/RD7_69") (pintype "bidirectional"))
    )
    (net (code "103") (name "unconnected-(IC_MAIN-OSC1{slash}CLKIN{slash}RC12-Pad49)") (class "Default")
      (node (ref "IC_MAIN") (pin "49") (pinfunction "OSC1/CLKIN/RC12_49") (pintype "bidirectional"))
    )
    (net (code "104") (name "unconnected-(IC_MAIN-OSC2{slash}CLKO{slash}RC15-Pad50)") (class "Default")
      (node (ref "IC_MAIN") (pin "50") (pinfunction "OSC2/CLKO/RC15_50") (pintype "bidirectional"))
    )
    (net (code "105") (name "unconnected-(IC_MAIN-PGC2{slash}EMUC2{slash}SOSCO{slash}T1CK{slash}CN0{slash}RC14-Pad60)") (class "Default")
      (node (ref "IC_MAIN") (pin "60") (pinfunction "PGC2/EMUC2/SOSCO/T1CK/CN0/RC14_60") (pintype "bidirectional"))
    )
    (net (code "106") (name "unconnected-(IC_MAIN-PGD2{slash}EMUD2{slash}SOSCI{slash}CN1{slash}RC13-Pad59)") (class "Default")
      (node (ref "IC_MAIN") (pin "59") (pinfunction "PGD2/EMUD2/SOSCI/CN1/RC13_59") (pintype "bidirectional"))
    )
    (net (code "107") (name "unconnected-(IC_MAIN-RG0-Pad75)") (class "Default")
      (node (ref "IC_MAIN") (pin "75") (pinfunction "RG0_75") (pintype "bidirectional"))
    )
    (net (code "108") (name "unconnected-(IC_MAIN-RG1-Pad74)") (class "Default")
      (node (ref "IC_MAIN") (pin "74") (pinfunction "RG1_74") (pintype "bidirectional"))
    )
    (net (code "109") (name "unconnected-(IC_MAIN-SCK1{slash}INT0{slash}RF6-Pad45)") (class "Default")
      (node (ref "IC_MAIN") (pin "45") (pinfunction "SCK1/INT0/RF6_45") (pintype "bidirectional"))
    )
    (net (code "110") (name "unconnected-(IC_MAIN-SCK2{slash}CN8{slash}RG6-Pad6)") (class "Default")
      (node (ref "IC_MAIN") (pin "6") (pinfunction "SCK2/CN8/RG6_6") (pintype "bidirectional"))
    )
    (net (code "111") (name "unconnected-(IC_MAIN-SCL1{slash}RG2-Pad47)") (class "Default")
      (node (ref "IC_MAIN") (pin "47") (pinfunction "SCL1/RG2_47") (pintype "bidirectional"))
    )
    (net (code "112") (name "unconnected-(IC_MAIN-SCL2{slash}INT3{slash}RA2-Pad52)") (class "Default")
      (node (ref "IC_MAIN") (pin "52") (pinfunction "SCL2/INT3/RA2_52") (pintype "bidirectional"))
    )
    (net (code "113") (name "unconnected-(IC_MAIN-SDA1{slash}RG3-Pad46)") (class "Default")
      (node (ref "IC_MAIN") (pin "46") (pinfunction "SDA1/RG3_46") (pintype "bidirectional"))
    )
    (net (code "114") (name "unconnected-(IC_MAIN-SDA2{slash}INT4{slash}RA3-Pad53)") (class "Default")
      (node (ref "IC_MAIN") (pin "53") (pinfunction "SDA2/INT4/RA3_53") (pintype "bidirectional"))
    )
    (net (code "115") (name "unconnected-(IC_MAIN-SDI1{slash}RF7-Pad44)") (class "Default")
      (node (ref "IC_MAIN") (pin "44") (pinfunction "SDI1/RF7_44") (pintype "bidirectional"))
    )
    (net (code "116") (name "unconnected-(IC_MAIN-SDI2{slash}CN9{slash}RG7-Pad7)") (class "Default")
      (node (ref "IC_MAIN") (pin "7") (pinfunction "SDI2/CN9/RG7_7") (pintype "bidirectional"))
    )
    (net (code "117") (name "unconnected-(IC_MAIN-SDO1{slash}RF8-Pad43)") (class "Default")
      (node (ref "IC_MAIN") (pin "43") (pinfunction "SDO1/RF8_43") (pintype "bidirectional"))
    )
    (net (code "118") (name "unconnected-(IC_MAIN-SDO2{slash}CN10{slash}RG8-Pad8)") (class "Default")
      (node (ref "IC_MAIN") (pin "8") (pinfunction "SDO2/CN10/RG8_8") (pintype "bidirectional"))
    )
    (net (code "119") (name "unconnected-(IC_MAIN-TCK{slash}AN12{slash}RB12-Pad33)") (class "Default")
      (node (ref "IC_MAIN") (pin "33") (pinfunction "TCK/AN12/RB12_33") (pintype "bidirectional"))
    )
    (net (code "120") (name "unconnected-(IC_MAIN-TDI{slash}AN13{slash}RB13-Pad34)") (class "Default")
      (node (ref "IC_MAIN") (pin "34") (pinfunction "TDI/AN13/RB13_34") (pintype "bidirectional"))
    )
    (net (code "121") (name "unconnected-(IC_MAIN-TDO{slash}~{FLTB{slash}INT2{slash}RE9}-Pad14)") (class "Default")
      (node (ref "IC_MAIN") (pin "14") (pinfunction "TDO/~{FLTB/INT2/RE9}_14") (pintype "bidirectional"))
    )
    (net (code "122") (name "unconnected-(IC_MAIN-TMS{slash}~{FLTA{slash}INT1{slash}RE8}-Pad13)") (class "Default")
      (node (ref "IC_MAIN") (pin "13") (pinfunction "TMS/~{FLTA/INT1/RE8}_13") (pintype "bidirectional"))
    )
    (net (code "123") (name "unconnected-(IC_MAIN-U1RX{slash}RF2-Pad42)") (class "Default")
      (node (ref "IC_MAIN") (pin "42") (pinfunction "U1RX/RF2_42") (pintype "bidirectional"))
    )
    (net (code "124") (name "unconnected-(IC_MAIN-U1TX{slash}RF3-Pad41)") (class "Default")
      (node (ref "IC_MAIN") (pin "41") (pinfunction "U1TX/RF3_41") (pintype "bidirectional"))
    )
    (net (code "125") (name "unconnected-(IC_MAIN-U2RX{slash}CN17{slash}RF4-Pad39)") (class "Default")
      (node (ref "IC_MAIN") (pin "39") (pinfunction "U2RX/CN17/RF4_39") (pintype "bidirectional"))
    )
    (net (code "126") (name "unconnected-(IC_MAIN-U2TX{slash}CN18{slash}RF5-Pad40)") (class "Default")
      (node (ref "IC_MAIN") (pin "40") (pinfunction "U2TX/CN18/RF5_40") (pintype "bidirectional"))
    )
    (net (code "127") (name "unconnected-(IC_MAIN-VREF+{slash}RA10-Pad24)") (class "Default")
      (node (ref "IC_MAIN") (pin "24") (pinfunction "VREF+/RA10_24") (pintype "bidirectional"))
    )
    (net (code "128") (name "unconnected-(IC_MAIN-VREF-{slash}RA9-Pad23)") (class "Default")
      (node (ref "IC_MAIN") (pin "23") (pinfunction "VREF-/RA9_23") (pintype "bidirectional"))
    )
    (net (code "129") (name "unconnected-(IC_MAIN-~{SS2{slash}CN11{slash}RG9}-Pad10)") (class "Default")
      (node (ref "IC_MAIN") (pin "10") (pinfunction "~{SS2/CN11/RG9}_10") (pintype "bidirectional"))
    )
    (net (code "130") (name "unconnected-(IC_MAIN-~{U2CTS{slash}AN8{slash}RB8}-Pad27)") (class "Default")
      (node (ref "IC_MAIN") (pin "27") (pinfunction "~{U2CTS/AN8/RB8}_27") (pintype "bidirectional"))
    )
    (net (code "131") (name "unconnected-(IC_MAIN-~{U2RTS{slash}AN14{slash}RB14}-Pad35)") (class "Default")
      (node (ref "IC_MAIN") (pin "35") (pinfunction "~{U2RTS/AN14/RB14}_35") (pintype "bidirectional"))
    )
    (net (code "132") (name "unconnected-(IC_R_I_D-NC1-Pad1)") (class "Default")
      (node (ref "IC_R_I_D") (pin "1") (pinfunction "NC1_1") (pintype "no_connect"))
    )
    (net (code "133") (name "unconnected-(IC_R_I_D-NC4-Pad4)") (class "Default")
      (node (ref "IC_R_I_D") (pin "4") (pinfunction "NC4_4") (pintype "no_connect"))
    )
    (net (code "134") (name "unconnected-(IC_R_I_D-NC7-Pad7)") (class "Default")
      (node (ref "IC_R_I_D") (pin "7") (pinfunction "NC7_7") (pintype "no_connect"))
    )
    (net (code "135") (name "unconnected-(IC_R_I_U-NC1-Pad1)") (class "Default")
      (node (ref "IC_R_I_U") (pin "1") (pinfunction "NC1_1") (pintype "no_connect"))
    )
    (net (code "136") (name "unconnected-(IC_R_I_U-NC4-Pad4)") (class "Default")
      (node (ref "IC_R_I_U") (pin "4") (pinfunction "NC4_4") (pintype "no_connect"))
    )
    (net (code "137") (name "unconnected-(IC_R_I_U-NC7-Pad7)") (class "Default")
      (node (ref "IC_R_I_U") (pin "7") (pinfunction "NC7_7") (pintype "no_connect"))
    )
    (net (code "138") (name "unconnected-(IC_R_O_D-NC1-Pad1)") (class "Default")
      (node (ref "IC_R_O_D") (pin "1") (pinfunction "NC1_1") (pintype "no_connect"))
    )
    (net (code "139") (name "unconnected-(IC_R_O_D-NC4-Pad4)") (class "Default")
      (node (ref "IC_R_O_D") (pin "4") (pinfunction "NC4_4") (pintype "no_connect"))
    )
    (net (code "140") (name "unconnected-(IC_R_O_D-NC7-Pad7)") (class "Default")
      (node (ref "IC_R_O_D") (pin "7") (pinfunction "NC7_7") (pintype "no_connect"))
    )
    (net (code "141") (name "unconnected-(IC_R_O_U-NC1-Pad1)") (class "Default")
      (node (ref "IC_R_O_U") (pin "1") (pinfunction "NC1_1") (pintype "no_connect"))
    )
    (net (code "142") (name "unconnected-(IC_R_O_U-NC4-Pad4)") (class "Default")
      (node (ref "IC_R_O_U") (pin "4") (pinfunction "NC4_4") (pintype "no_connect"))
    )
    (net (code "143") (name "unconnected-(IC_R_O_U-NC7-Pad7)") (class "Default")
      (node (ref "IC_R_O_U") (pin "7") (pinfunction "NC7_7") (pintype "no_connect"))
    )
  )
)
